# J2_Control_Panel.net
KiCad netlist of a schematic drawn in Altium Designer
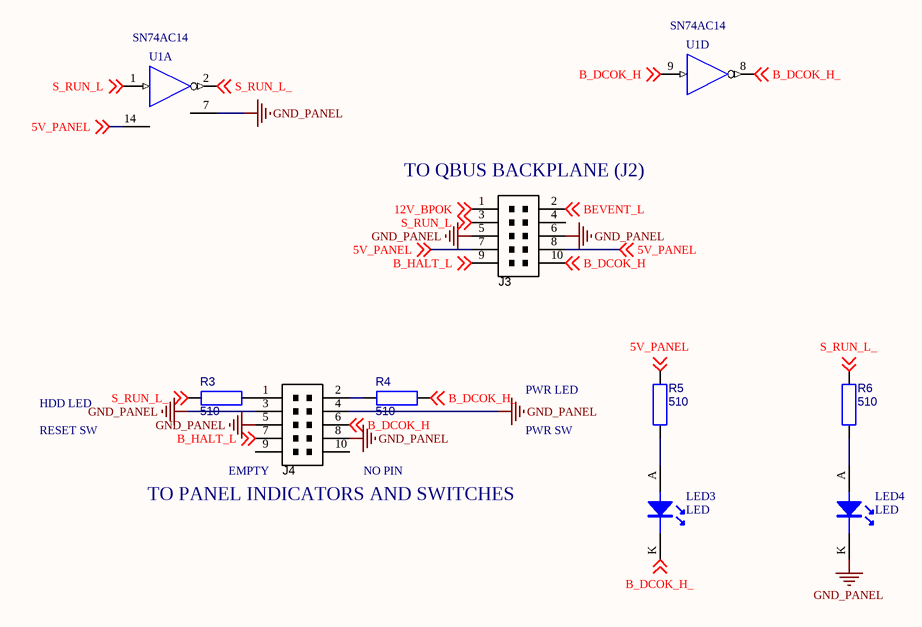
[diagram p0: J2 Control Panel.SchDoc]

(export (version "E")
  (design (tool "Eeschema 10.0.6"))
  (components
    (comp (ref "J3")
      (value "shrouded box header")
      (footprint "10P_PCB_HEADER_BRD_MNT")
      (description "Header THD 10 POS Double-row 2.54mm pitch")
      (libsource (lib "PBL - Connectors") (part "CONN_HEADER_2x5P_0.100in_Male"))
    )
    (comp (ref "J4")
      (value "shrouded box header")
      (footprint "10P_PCB_HEADER_BRD_MNT")
      (description "Header THD 10 POS Double-row 2.54mm pitch")
      (libsource (lib "PBL - Connectors") (part "CONN_HEADER_2x5P_0.100in_Male"))
    )
    (comp (ref "LED3") (value "LED") (footprint "LTST-C170") (libsource (lib "TRA1404(DIFT2)") (part "LED")))
    (comp (ref "LED4") (value "LED") (footprint "LTST-C170") (libsource (lib "TRA1404(DIFT2)") (part "LED")))
    (comp (ref "R3")
      (value "510")
      (footprint "RESC2012X70N")
      (description "RESISTOR")
      (libsource (lib "SCH") (part "RES2"))
    )
    (comp (ref "R4")
      (value "510")
      (footprint "RESC2012X70N")
      (description "RESISTOR")
      (libsource (lib "SCH") (part "RES2"))
    )
    (comp (ref "R5")
      (value "510")
      (footprint "RESC2012X70N")
      (description "RESISTOR")
      (libsource (lib "SCH") (part "RES2"))
    )
    (comp (ref "R6")
      (value "510")
      (footprint "RESC2012X70N")
      (description "RESISTOR")
      (libsource (lib "SCH") (part "RES2"))
    )
    (comp (ref "U1")
      (value "SN74AC14")
      (footprint "J014C")
      (description "Hex Schmitt-Trigger Inverter")
      (fields (field (name "PUBLISHER") "Altium Limited"))
      (libsource (lib "TI Logic Gate 1") (part "SN74AHCT14D"))
    )
  )
  (nets
    (net (code "1") (name "5V_PANEL") (class "Default")
      (node (ref "J3") (pin "7") (pinfunction "7_7") (pintype "passive"))
      (node (ref "J3") (pin "8") (pinfunction "8_8") (pintype "passive"))
      (node (ref "R5") (pin "1") (pintype "passive"))
      (node (ref "U1") (pin "14") (pinfunction "VCC_14") (pintype "power_in"))
    )
    (net (code "2") (name "12V_BPOK") (class "Default")
      (node (ref "J3") (pin "1") (pinfunction "1_1") (pintype "passive"))
    )
    (net (code "3") (name "BEVENT_L") (class "Default")
      (node (ref "J3") (pin "2") (pinfunction "2_2") (pintype "passive"))
    )
    (net (code "4") (name "B_DCOK_H") (class "Default")
      (node (ref "J3") (pin "10") (pinfunction "10_10") (pintype "passive"))
      (node (ref "J4") (pin "6") (pinfunction "6_6") (pintype "passive"))
      (node (ref "U1") (pin "9") (pinfunction "A_9") (pintype "input"))
    )
    (net (code "5") (name "B_DCOK_H_") (class "Default")
      (node (ref "LED3") (pin "K") (pinfunction "1_K") (pintype "passive"))
      (node (ref "R4") (pin "2") (pintype "passive"))
      (node (ref "U1") (pin "8") (pinfunction "Y_8") (pintype "output"))
    )
    (net (code "6") (name "B_HALT_L") (class "Default")
      (node (ref "J3") (pin "9") (pinfunction "9_9") (pintype "passive"))
      (node (ref "J4") (pin "7") (pinfunction "7_7") (pintype "passive"))
    )
    (net (code "7") (name "GND") (class "Default")
      (node (ref "U1") (pin "7") (pinfunction "GND_PANEL_7") (pintype "power_in"))
    )
    (net (code "8") (name "GND_PANEL") (class "Default")
      (node (ref "J3") (pin "5") (pinfunction "5_5") (pintype "passive"))
      (node (ref "J3") (pin "6") (pinfunction "6_6") (pintype "passive"))
      (node (ref "J4") (pin "3") (pinfunction "3_3") (pintype "passive"))
      (node (ref "J4") (pin "4") (pinfunction "4_4") (pintype "passive"))
      (node (ref "J4") (pin "5") (pinfunction "5_5") (pintype "passive"))
      (node (ref "J4") (pin "8") (pinfunction "8_8") (pintype "passive"))
      (node (ref "LED4") (pin "K") (pinfunction "1_K") (pintype "passive"))
      (node (ref "U1") (pin "7") (pinfunction "GND_PANEL_7") (pintype "power_in"))
    )
    (net (code "9") (name "Net-(J4-Pad1)") (class "Default")
      (node (ref "J4") (pin "1") (pinfunction "1_1") (pintype "passive"))
      (node (ref "R3") (pin "2") (pintype "passive"))
    )
    (net (code "10") (name "Net-(J4-Pad2)") (class "Default")
      (node (ref "J4") (pin "2") (pinfunction "2_2") (pintype "passive"))
      (node (ref "R4") (pin "1") (pintype "passive"))
    )
    (net (code "11") (name "Net-(LED3-2)") (class "Default")
      (node (ref "LED3") (pin "A") (pinfunction "2_A") (pintype "passive"))
      (node (ref "R5") (pin "2") (pintype "passive"))
    )
    (net (code "12") (name "Net-(LED4-2)") (class "Default")
      (node (ref "LED4") (pin "A") (pinfunction "2_A") (pintype "passive"))
      (node (ref "R6") (pin "2") (pintype "passive"))
    )
    (net (code "13") (name "S_RUN_L") (class "Default")
      (node (ref "J3") (pin "3") (pinfunction "3_3") (pintype "passive"))
      (node (ref "U1") (pin "1") (pinfunction "A_1") (pintype "input"))
    )
    (net (code "14") (name "S_RUN_L_") (class "Default")
      (node (ref "R3") (pin "1") (pintype "passive"))
      (node (ref "R6") (pin "1") (pintype "passive"))
      (node (ref "U1") (pin "2") (pinfunction "Y_2") (pintype "output"))
    )
    (net (code "15") (name "VCC") (class "Default")
      (node (ref "U1") (pin "14") (pinfunction "VCC_14") (pintype "power_in"))
    )
    (net (code "16") (name "unconnected-(J3-Pad4)") (class "Default")
      (node (ref "J3") (pin "4") (pinfunction "4_4") (pintype "passive"))
    )
    (net (code "17") (name "unconnected-(J4-Pad9)") (class "Default")
      (node (ref "J4") (pin "9") (pinfunction "9_9") (pintype "passive"))
    )
    (net (code "18") (name "unconnected-(J4-Pad10)") (class "Default")
      (node (ref "J4") (pin "10") (pinfunction "10_10") (pintype "passive"))
    )
  )
)
